# schematic.net
KiCad netlist of a schematic drawn in EAGLE
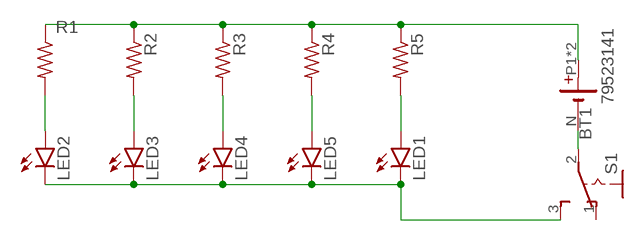
[diagram p0: schematic, sheet 1]

(export (version "E")
  (design (tool "Eeschema 10.0.6"))
  (components
    (comp (ref "BT1")
      (value "79523141")
      (footprint "eagle-import:79523141")
      (fields
        (field (name "DIGIKEY_PART_NO") "732-12323-2-ND")
        (field (name "MANUFACTURER") "Wurth Electronics Inc.")
        (field (name "CREATED_BY") "PCBLayout.com")
      )
      (libsource (lib "eagle-import") (part "79523141"))
    )
    (comp (ref "LED1")
      (value "LED3MM")
      (footprint "eagle-import:LED3MM")
      (libsource (lib "eagle-import") (part "LED3MM"))
    )
    (comp (ref "LED2")
      (value "LED3MM")
      (footprint "eagle-import:LED3MM")
      (libsource (lib "eagle-import") (part "LED3MM"))
    )
    (comp (ref "LED3")
      (value "LED3MM")
      (footprint "eagle-import:LED3MM")
      (libsource (lib "eagle-import") (part "LED3MM"))
    )
    (comp (ref "LED4")
      (value "LED3MM")
      (footprint "eagle-import:LED3MM")
      (libsource (lib "eagle-import") (part "LED3MM"))
    )
    (comp (ref "LED5")
      (value "LED3MM")
      (footprint "eagle-import:LED3MM")
      (libsource (lib "eagle-import") (part "LED3MM"))
    )
    (comp (ref "R1")
      (value "R-US_0204/5")
      (footprint "eagle-import:0204_5")
      (libsource (lib "eagle-import") (part "R-US_0204/5"))
    )
    (comp (ref "R2")
      (value "R-US_0204/5")
      (footprint "eagle-import:0204_5")
      (libsource (lib "eagle-import") (part "R-US_0204/5"))
    )
    (comp (ref "R3")
      (value "R-US_0204/5")
      (footprint "eagle-import:0204_5")
      (libsource (lib "eagle-import") (part "R-US_0204/5"))
    )
    (comp (ref "R4")
      (value "R-US_0204/5")
      (footprint "eagle-import:0204_5")
      (libsource (lib "eagle-import") (part "R-US_0204/5"))
    )
    (comp (ref "R5")
      (value "R-US_0204/5")
      (footprint "eagle-import:0204_5")
      (libsource (lib "eagle-import") (part "R-US_0204/5"))
    )
    (comp (ref "S1")
      (value "M251")
      (footprint "eagle-import:M251")
      (libsource (lib "eagle-import") (part "M251"))
    )
  )
  (nets
    (net (code "1") (name "Net-(BT1-+-PadP1)") (class "Default")
      (node (ref "BT1") (pin "P1") (pinfunction "+_P1") (pintype "passive"))
      (node (ref "BT1") (pin "P2") (pinfunction "+_P2") (pintype "passive"))
      (node (ref "R1") (pin "1") (pinfunction "1_1") (pintype "passive"))
      (node (ref "R2") (pin "1") (pinfunction "1_1") (pintype "passive"))
      (node (ref "R3") (pin "1") (pinfunction "1_1") (pintype "passive"))
      (node (ref "R4") (pin "1") (pinfunction "1_1") (pintype "passive"))
      (node (ref "R5") (pin "1") (pinfunction "1_1") (pintype "passive"))
    )
    (net (code "2") (name "Net-(BT1--)") (class "Default")
      (node (ref "BT1") (pin "N") (pinfunction "-_N") (pintype "passive"))
      (node (ref "S1") (pin "2") (pinfunction "P_2") (pintype "passive"))
    )
    (net (code "3") (name "Net-(LED1-C)") (class "Default")
      (node (ref "LED1") (pin "K") (pinfunction "C_K") (pintype "passive"))
      (node (ref "LED2") (pin "K") (pinfunction "C_K") (pintype "passive"))
      (node (ref "LED3") (pin "K") (pinfunction "C_K") (pintype "passive"))
      (node (ref "LED4") (pin "K") (pinfunction "C_K") (pintype "passive"))
      (node (ref "LED5") (pin "K") (pinfunction "C_K") (pintype "passive"))
      (node (ref "S1") (pin "3") (pinfunction "S_3") (pintype "passive"))
    )
    (net (code "4") (name "Net-(LED1-PadA)") (class "Default")
      (node (ref "LED1") (pin "A") (pinfunction "A_A") (pintype "passive"))
      (node (ref "R5") (pin "2") (pinfunction "2_2") (pintype "passive"))
    )
    (net (code "5") (name "Net-(LED2-PadA)") (class "Default")
      (node (ref "LED2") (pin "A") (pinfunction "A_A") (pintype "passive"))
      (node (ref "R1") (pin "2") (pinfunction "2_2") (pintype "passive"))
    )
    (net (code "6") (name "Net-(LED3-PadA)") (class "Default")
      (node (ref "LED3") (pin "A") (pinfunction "A_A") (pintype "passive"))
      (node (ref "R2") (pin "2") (pinfunction "2_2") (pintype "passive"))
    )
    (net (code "7") (name "Net-(LED4-PadA)") (class "Default")
      (node (ref "LED4") (pin "A") (pinfunction "A_A") (pintype "passive"))
      (node (ref "R3") (pin "2") (pinfunction "2_2") (pintype "passive"))
    )
    (net (code "8") (name "Net-(LED5-PadA)") (class "Default")
      (node (ref "LED5") (pin "A") (pinfunction "A_A") (pintype "passive"))
      (node (ref "R4") (pin "2") (pinfunction "2_2") (pintype "passive"))
    )
    (net (code "9") (name "unconnected-(S1-O-Pad1)") (class "Default")
      (node (ref "S1") (pin "1") (pinfunction "O_1") (pintype "passive"))
    )
  )
)
